# Sheet5.net
KiCad netlist of a schematic drawn in Altium Designer
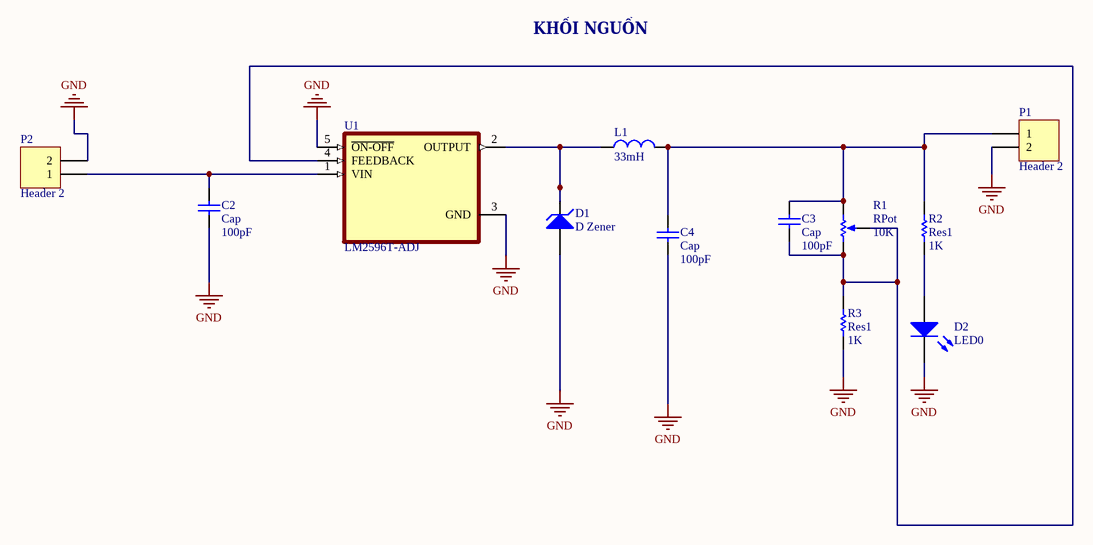
[diagram p0: Sheet5.SchDoc]

(export (version "E")
  (design (tool "Eeschema 10.0.6"))
  (components
    (comp (ref "C2")
      (value "Cap")
      (footprint "RAD-0.3")
      (description "Capacitor")
      (fields (field (name "ALTIUM_VALUE") "100pF") (field (name "PUBLISHER") "Altium Limited"))
      (libsource (lib "Miscellaneous Devices") (part "Cap"))
    )
    (comp (ref "C3")
      (value "Cap")
      (footprint "RAD-0.3")
      (description "Capacitor")
      (fields (field (name "ALTIUM_VALUE") "100pF") (field (name "PUBLISHER") "Altium Limited"))
      (libsource (lib "Miscellaneous Devices") (part "Cap"))
    )
    (comp (ref "C4")
      (value "Cap")
      (footprint "RAD-0.3")
      (description "Capacitor")
      (fields (field (name "ALTIUM_VALUE") "100pF") (field (name "PUBLISHER") "Altium Limited"))
      (libsource (lib "Miscellaneous Devices") (part "Cap"))
    )
    (comp (ref "D1")
      (value "D Zener")
      (footprint "DIODE-0.7")
      (description "Zener Diode")
      (fields (field (name "PUBLISHER") "Altium Limited"))
      (libsource (lib "Miscellaneous Devices") (part "D Zener"))
    )
    (comp (ref "D2")
      (value "LED0")
      (footprint "LED-0")
      (description "Typical INFRARED GaAs LED")
      (fields (field (name "PUBLISHER") "Altium Limited"))
      (libsource (lib "Miscellaneous Devices") (part "LED0"))
    )
    (comp (ref "L1")
      (value "33mH")
      (footprint "L/0.4")
      (description "Inductor")
      (libsource (lib "library2") (part "L1"))
    )
    (comp (ref "P1")
      (value "Header 2")
      (footprint "HDR1X2")
      (description "Header, 2-Pin")
      (fields (field (name "PUBLISHER") "Altium Limited"))
      (libsource (lib "Miscellaneous Connectors") (part "Header 2"))
    )
    (comp (ref "P2")
      (value "Header 2")
      (footprint "HDR1X2")
      (description "Header, 2-Pin")
      (fields (field (name "PUBLISHER") "Altium Limited"))
      (libsource (lib "") (part "Header 2_1"))
    )
    (comp (ref "R1")
      (value "RPot")
      (footprint "VR5")
      (description "Potentiometer")
      (fields (field (name "ALTIUM_VALUE") "10K") (field (name "PUBLISHER") "Altium Limited"))
      (libsource (lib "Miscellaneous Devices") (part "RPot"))
    )
    (comp (ref "R2")
      (value "Res1")
      (footprint "AXIAL-0.3")
      (description "Resistor")
      (fields (field (name "ALTIUM_VALUE") "1K") (field (name "PUBLISHER") "Altium Limited"))
      (libsource (lib "Miscellaneous Devices") (part "Res1"))
    )
    (comp (ref "R3")
      (value "Res1")
      (footprint "AXIAL-0.3")
      (description "Resistor")
      (fields (field (name "ALTIUM_VALUE") "1K") (field (name "PUBLISHER") "Altium Limited"))
      (libsource (lib "Miscellaneous Devices") (part "Res1"))
    )
    (comp (ref "U1")
      (value "LM2596T-ADJ")
      (footprint "TO170P1016X470X2092-5")
      (description "SIMPLE SWITCHER&reg; 4.5V to 40V, 3A Low Component Count Step-Down Regulator 5-TO-220 -40 to 125")
      (fields (field (name "MF") "Texas Instruments"))
      (libsource (lib "LM2596T-ADJ") (part "LM2596T-ADJ"))
    )
  )
  (nets
    (net (code "1") (name "GND") (class "Default")
      (node (ref "C2") (pin "1") (pinfunction "1_1") (pintype "passive"))
      (node (ref "C4") (pin "1") (pinfunction "1_1") (pintype "passive"))
      (node (ref "D1") (pin "1") (pinfunction "A_1") (pintype "passive"))
      (node (ref "D2") (pin "2") (pinfunction "K_2") (pintype "passive"))
      (node (ref "P1") (pin "2") (pinfunction "2_2") (pintype "passive"))
      (node (ref "P2") (pin "2") (pinfunction "2_2") (pintype "passive"))
      (node (ref "R3") (pin "1") (pinfunction "1_1") (pintype "passive"))
      (node (ref "U1") (pin "3") (pinfunction "GND_3") (pintype "power_in"))
      (node (ref "U1") (pin "5") (pinfunction "~{ON-OFF}_5") (pintype "input"))
    )
    (net (code "2") (name "Net-(D1-K)") (class "Default")
      (node (ref "D1") (pin "2") (pinfunction "K_2") (pintype "passive"))
      (node (ref "L1") (pin "1") (pinfunction "1_1") (pintype "passive"))
      (node (ref "U1") (pin "2") (pinfunction "OUTPUT_2") (pintype "output"))
    )
    (net (code "3") (name "Net-(D2-A)") (class "Default")
      (node (ref "D2") (pin "1") (pinfunction "A_1") (pintype "passive"))
      (node (ref "R2") (pin "1") (pinfunction "1_1") (pintype "passive"))
    )
    (net (code "4") (name "Net-(R1-BOT)") (class "Default")
      (node (ref "C3") (pin "2") (pinfunction "2_2") (pintype "passive"))
      (node (ref "C4") (pin "2") (pinfunction "2_2") (pintype "passive"))
      (node (ref "L1") (pin "2") (pinfunction "2_2") (pintype "passive"))
      (node (ref "P1") (pin "1") (pinfunction "1_1") (pintype "passive"))
      (node (ref "R1") (pin "2") (pinfunction "BOT_2") (pintype "passive"))
      (node (ref "R2") (pin "2") (pinfunction "2_2") (pintype "passive"))
    )
    (net (code "5") (name "Net-(R1-TAP)") (class "Default")
      (node (ref "C3") (pin "1") (pinfunction "1_1") (pintype "passive"))
      (node (ref "R1") (pin "1") (pinfunction "TOP_1") (pintype "passive"))
      (node (ref "R1") (pin "3") (pinfunction "TAP_3") (pintype "passive"))
      (node (ref "R3") (pin "2") (pinfunction "2_2") (pintype "passive"))
      (node (ref "U1") (pin "4") (pinfunction "FEEDBACK_4") (pintype "input"))
    )
    (net (code "6") (name "Net-(U1-VIN)") (class "Default")
      (node (ref "C2") (pin "2") (pinfunction "2_2") (pintype "passive"))
      (node (ref "P2") (pin "1") (pinfunction "1_1") (pintype "passive"))
      (node (ref "U1") (pin "1") (pinfunction "VIN_1") (pintype "input"))
    )
  )
)
